# WALL_POWER.net
KiCad netlist of a schematic drawn in Altium Designer
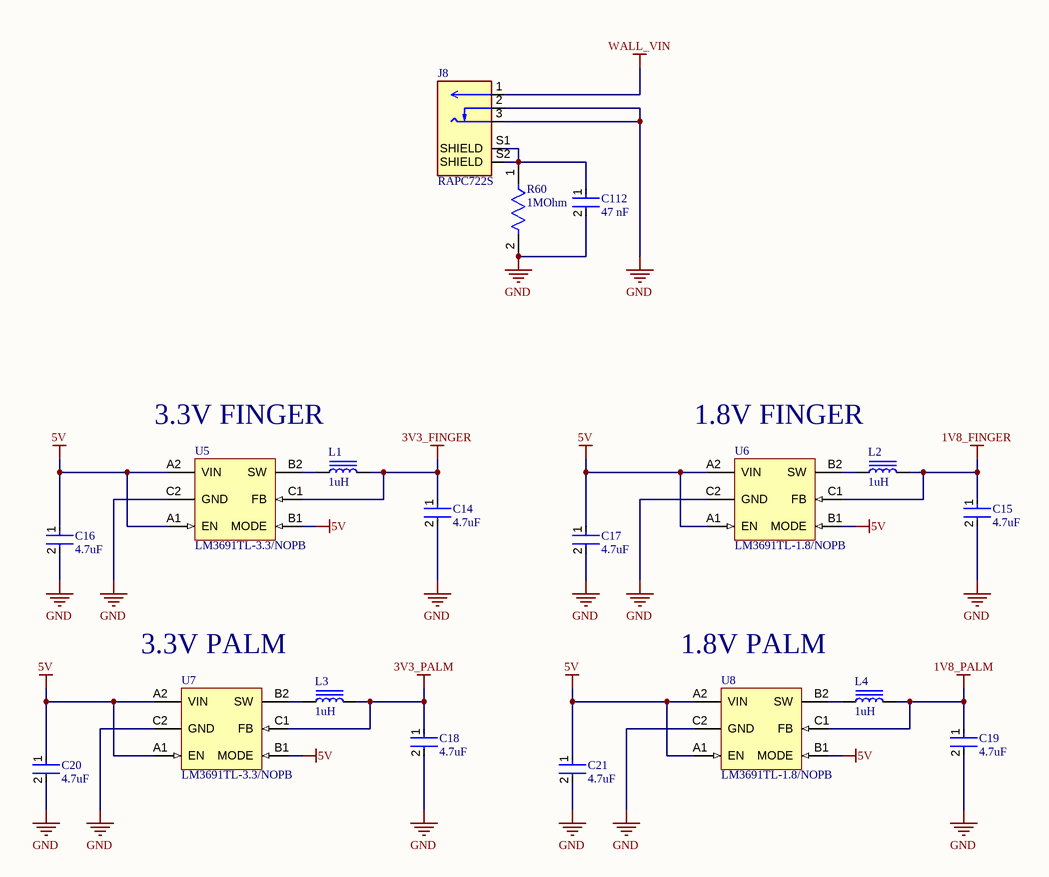
[diagram p0: WALL_POWER.SchDoc]

(export (version "E")
  (design (tool "Eeschema 10.0.6"))
  (components
    (comp (ref "C14")
      (value "4.7uF")
      (footprint "FP-CL828-IPC_C")
      (description "Cap Ceramic 4.7uF 10V X5R ±10% SMD 0402 +85°C Paper T/R")
      (fields (field (name "TOLERANCE") "10%"))
      (libsource (lib "Altium Content Vault") (part "b4654b650e69147ec39a6b967a45e02"))
    )
    (comp (ref "C15")
      (value "4.7uF")
      (footprint "FP-CL828-IPC_C")
      (description "Cap Ceramic 4.7uF 10V X5R ±10% SMD 0402 +85°C Paper T/R")
      (fields (field (name "TOLERANCE") "10%"))
      (libsource (lib "Altium Content Vault") (part "b4654b650e69147ec39a6b967a45e02"))
    )
    (comp (ref "C16")
      (value "4.7uF")
      (footprint "FP-CL828-IPC_C")
      (description "Cap Ceramic 4.7uF 10V X5R ±10% SMD 0402 +85°C Paper T/R")
      (fields (field (name "TOLERANCE") "10%"))
      (libsource (lib "Altium Content Vault") (part "b4654b650e69147ec39a6b967a45e02"))
    )
    (comp (ref "C17")
      (value "4.7uF")
      (footprint "FP-CL828-IPC_C")
      (description "Cap Ceramic 4.7uF 10V X5R ±10% SMD 0402 +85°C Paper T/R")
      (fields (field (name "TOLERANCE") "10%"))
      (libsource (lib "Altium Content Vault") (part "b4654b650e69147ec39a6b967a45e02"))
    )
    (comp (ref "C18")
      (value "4.7uF")
      (footprint "FP-CL828-IPC_C")
      (description "Cap Ceramic 4.7uF 10V X5R ±10% SMD 0402 +85°C Paper T/R")
      (fields (field (name "TOLERANCE") "10%"))
      (libsource (lib "Altium Content Vault") (part "b4654b650e69147ec39a6b967a45e02"))
    )
    (comp (ref "C19")
      (value "4.7uF")
      (footprint "FP-CL828-IPC_C")
      (description "Cap Ceramic 4.7uF 10V X5R ±10% SMD 0402 +85°C Paper T/R")
      (fields (field (name "TOLERANCE") "10%"))
      (libsource (lib "Altium Content Vault") (part "b4654b650e69147ec39a6b967a45e02"))
    )
    (comp (ref "C20")
      (value "4.7uF")
      (footprint "FP-CL828-IPC_C")
      (description "Cap Ceramic 4.7uF 10V X5R ±10% SMD 0402 +85°C Paper T/R")
      (fields (field (name "TOLERANCE") "10%"))
      (libsource (lib "Altium Content Vault") (part "b4654b650e69147ec39a6b967a45e02"))
    )
    (comp (ref "C21")
      (value "4.7uF")
      (footprint "FP-CL828-IPC_C")
      (description "Cap Ceramic 4.7uF 10V X5R ±10% SMD 0402 +85°C Paper T/R")
      (fields (field (name "TOLERANCE") "10%"))
      (libsource (lib "Altium Content Vault") (part "b4654b650e69147ec39a6b967a45e02"))
    )
    (comp (ref "C112")
      (value "47 nF")
      (footprint "FP-CC0402-MFG")
      (description "CAP CER 0.047UF 25V X7R 0402")
      (fields
        (field (name "MANUFACTURER PART NUMBER") "CC0402KRX7R8BB473")
        (field (name "MANUFACTURER") "YAGEO")
      )
      (libsource (lib "Altium Content Vault") (part "11868f565c42a9108669ba33697ecf6"))
    )
    (comp (ref "J8")
      (value "RAPC722S")
      (footprint "SWITCHCRAFT_RAPC722S")
      (description "Power Barrel Connector Jack 2.10mm ID (0.083), 5.50mm OD (0.217) Through Hole, Right Angle")
      (fields (field (name "DIGI-KEY_PART_NUMBER") "SC3723-ND") (field (name "MF") "Switchcraft Inc."))
      (libsource (lib "RAPC722S") (part "RAPC722S"))
    )
    (comp (ref "L1")
      (value "1uH")
      (footprint "IND 0603_1608 RF WW")
      (description "SMT Inductor")
      (fields (field (name "MANUFACTURER") "Taiyo Yuden") (field (name "PART NUMBER") "MCHK1608T1R0MKN"))
      (libsource (lib "Phalanx") (part "MCHK1608T1R0MKN"))
    )
    (comp (ref "L2")
      (value "1uH")
      (footprint "IND 0603_1608 RF WW")
      (description "SMT Inductor")
      (fields (field (name "MANUFACTURER") "Taiyo Yuden") (field (name "PART NUMBER") "MCHK1608T1R0MKN"))
      (libsource (lib "Phalanx") (part "MCHK1608T1R0MKN"))
    )
    (comp (ref "L3")
      (value "1uH")
      (footprint "IND 0603_1608 RF WW")
      (description "SMT Inductor")
      (fields (field (name "MANUFACTURER") "Taiyo Yuden") (field (name "PART NUMBER") "MCHK1608T1R0MKN"))
      (libsource (lib "Phalanx") (part "MCHK1608T1R0MKN"))
    )
    (comp (ref "L4")
      (value "1uH")
      (footprint "IND 0603_1608 RF WW")
      (description "SMT Inductor")
      (fields (field (name "MANUFACTURER") "Taiyo Yuden") (field (name "PART NUMBER") "MCHK1608T1R0MKN"))
      (libsource (lib "Phalanx") (part "MCHK1608T1R0MKN"))
    )
    (comp (ref "R60")
      (value "1MOhm")
      (footprint "FP-RMCF0402-MFG")
      (description "1MΩ ±1% 0.063W 0402 Thick Film Chip Resistor AEC-Q200 compliant")
      (fields (field (name "TOLERANCE") "1%"))
      (libsource (lib "Altium Content Vault") (part "1029c3af85768c4190bb7ad29bc67b5"))
    )
    (comp (ref "U5")
      (value "LM3691TL-3.3/NOPB")
      (footprint "YZR0006APAF")
      (fields (field (name "MANUFACTURER") "Texas Instruments"))
      (libsource (lib "Altium Content Vault") (part "PM-DCDC-LM3691-6"))
    )
    (comp (ref "U6")
      (value "LM3691TL-1.8/NOPB")
      (footprint "YZR0006APAF")
      (fields (field (name "MANUFACTURER") "Texas Instruments"))
      (libsource (lib "Altium Content Vault") (part "PM-DCDC-LM3691-6"))
    )
    (comp (ref "U7")
      (value "LM3691TL-3.3/NOPB")
      (footprint "YZR0006APAF")
      (fields (field (name "MANUFACTURER") "Texas Instruments"))
      (libsource (lib "Altium Content Vault") (part "PM-DCDC-LM3691-6"))
    )
    (comp (ref "U8")
      (value "LM3691TL-1.8/NOPB")
      (footprint "YZR0006APAF")
      (fields (field (name "MANUFACTURER") "Texas Instruments"))
      (libsource (lib "Altium Content Vault") (part "PM-DCDC-LM3691-6"))
    )
  )
  (nets
    (net (code "1") (name "1V8_FINGER") (class "Default")
      (node (ref "C15") (pin "1") (pinfunction "1_1") (pintype "passive"))
      (node (ref "L2") (pin "2") (pinfunction "2_2") (pintype "passive"))
      (node (ref "U6") (pin "C1") (pinfunction "FB_C1") (pintype "input"))
    )
    (net (code "2") (name "1V8_PALM") (class "Default")
      (node (ref "C19") (pin "1") (pinfunction "1_1") (pintype "passive"))
      (node (ref "L4") (pin "2") (pinfunction "2_2") (pintype "passive"))
      (node (ref "U8") (pin "C1") (pinfunction "FB_C1") (pintype "input"))
    )
    (net (code "3") (name "3V3_FINGER") (class "Default")
      (node (ref "C14") (pin "1") (pinfunction "1_1") (pintype "passive"))
      (node (ref "L1") (pin "2") (pinfunction "2_2") (pintype "passive"))
      (node (ref "U5") (pin "C1") (pinfunction "FB_C1") (pintype "input"))
    )
    (net (code "4") (name "3V3_PALM") (class "Default")
      (node (ref "C18") (pin "1") (pinfunction "1_1") (pintype "passive"))
      (node (ref "L3") (pin "2") (pinfunction "2_2") (pintype "passive"))
      (node (ref "U7") (pin "C1") (pinfunction "FB_C1") (pintype "input"))
    )
    (net (code "5") (name "5V") (class "Default")
      (node (ref "C16") (pin "1") (pinfunction "1_1") (pintype "passive"))
      (node (ref "C17") (pin "1") (pinfunction "1_1") (pintype "passive"))
      (node (ref "C20") (pin "1") (pinfunction "1_1") (pintype "passive"))
      (node (ref "C21") (pin "1") (pinfunction "1_1") (pintype "passive"))
      (node (ref "U5") (pin "A1") (pinfunction "EN_A1") (pintype "input"))
      (node (ref "U5") (pin "A2") (pinfunction "VIN_A2") (pintype "power_in"))
      (node (ref "U5") (pin "B1") (pinfunction "MODE_B1") (pintype "input"))
      (node (ref "U6") (pin "A1") (pinfunction "EN_A1") (pintype "input"))
      (node (ref "U6") (pin "A2") (pinfunction "VIN_A2") (pintype "power_in"))
      (node (ref "U6") (pin "B1") (pinfunction "MODE_B1") (pintype "input"))
      (node (ref "U7") (pin "A1") (pinfunction "EN_A1") (pintype "input"))
      (node (ref "U7") (pin "A2") (pinfunction "VIN_A2") (pintype "power_in"))
      (node (ref "U7") (pin "B1") (pinfunction "MODE_B1") (pintype "input"))
      (node (ref "U8") (pin "A1") (pinfunction "EN_A1") (pintype "input"))
      (node (ref "U8") (pin "A2") (pinfunction "VIN_A2") (pintype "power_in"))
      (node (ref "U8") (pin "B1") (pinfunction "MODE_B1") (pintype "input"))
    )
    (net (code "6") (name "GND") (class "Default")
      (node (ref "C112") (pin "2") (pinfunction "2_2") (pintype "passive"))
      (node (ref "C14") (pin "2") (pinfunction "2_2") (pintype "passive"))
      (node (ref "C15") (pin "2") (pinfunction "2_2") (pintype "passive"))
      (node (ref "C16") (pin "2") (pinfunction "2_2") (pintype "passive"))
      (node (ref "C17") (pin "2") (pinfunction "2_2") (pintype "passive"))
      (node (ref "C18") (pin "2") (pinfunction "2_2") (pintype "passive"))
      (node (ref "C19") (pin "2") (pinfunction "2_2") (pintype "passive"))
      (node (ref "C20") (pin "2") (pinfunction "2_2") (pintype "passive"))
      (node (ref "C21") (pin "2") (pinfunction "2_2") (pintype "passive"))
      (node (ref "J8") (pin "2") (pinfunction "SHUNT_2") (pintype "passive"))
      (node (ref "J8") (pin "3") (pinfunction "TIP_3") (pintype "passive"))
      (node (ref "R60") (pin "2") (pinfunction "2_2") (pintype "passive"))
      (node (ref "U5") (pin "C2") (pinfunction "GND_C2") (pintype "power_in"))
      (node (ref "U6") (pin "C2") (pinfunction "GND_C2") (pintype "power_in"))
      (node (ref "U7") (pin "C2") (pinfunction "GND_C2") (pintype "power_in"))
      (node (ref "U8") (pin "C2") (pinfunction "GND_C2") (pintype "power_in"))
    )
    (net (code "7") (name "Net-(C112-Pad1)") (class "Default")
      (node (ref "C112") (pin "1") (pinfunction "1_1") (pintype "passive"))
      (node (ref "J8") (pin "S1") (pinfunction "SHIELD_S1") (pintype "passive"))
      (node (ref "J8") (pin "S2") (pinfunction "SHIELD_S2") (pintype "passive"))
      (node (ref "R60") (pin "1") (pinfunction "1_1") (pintype "passive"))
    )
    (net (code "8") (name "Net-(U5-SW)") (class "Default")
      (node (ref "L1") (pin "1") (pinfunction "1_1") (pintype "passive"))
      (node (ref "U5") (pin "B2") (pinfunction "SW_B2") (pintype "power_in"))
    )
    (net (code "9") (name "Net-(U6-SW)") (class "Default")
      (node (ref "L2") (pin "1") (pinfunction "1_1") (pintype "passive"))
      (node (ref "U6") (pin "B2") (pinfunction "SW_B2") (pintype "power_in"))
    )
    (net (code "10") (name "Net-(U7-SW)") (class "Default")
      (node (ref "L3") (pin "1") (pinfunction "1_1") (pintype "passive"))
      (node (ref "U7") (pin "B2") (pinfunction "SW_B2") (pintype "power_in"))
    )
    (net (code "11") (name "Net-(U8-SW)") (class "Default")
      (node (ref "L4") (pin "1") (pinfunction "1_1") (pintype "passive"))
      (node (ref "U8") (pin "B2") (pinfunction "SW_B2") (pintype "power_in"))
    )
    (net (code "12") (name "WALL_VIN") (class "Default")
      (node (ref "J8") (pin "1") (pinfunction "PIN_1") (pintype "passive"))
    )
  )
)
